# SPI_Level_Shifter.net
KiCad netlist of a schematic drawn in EAGLE
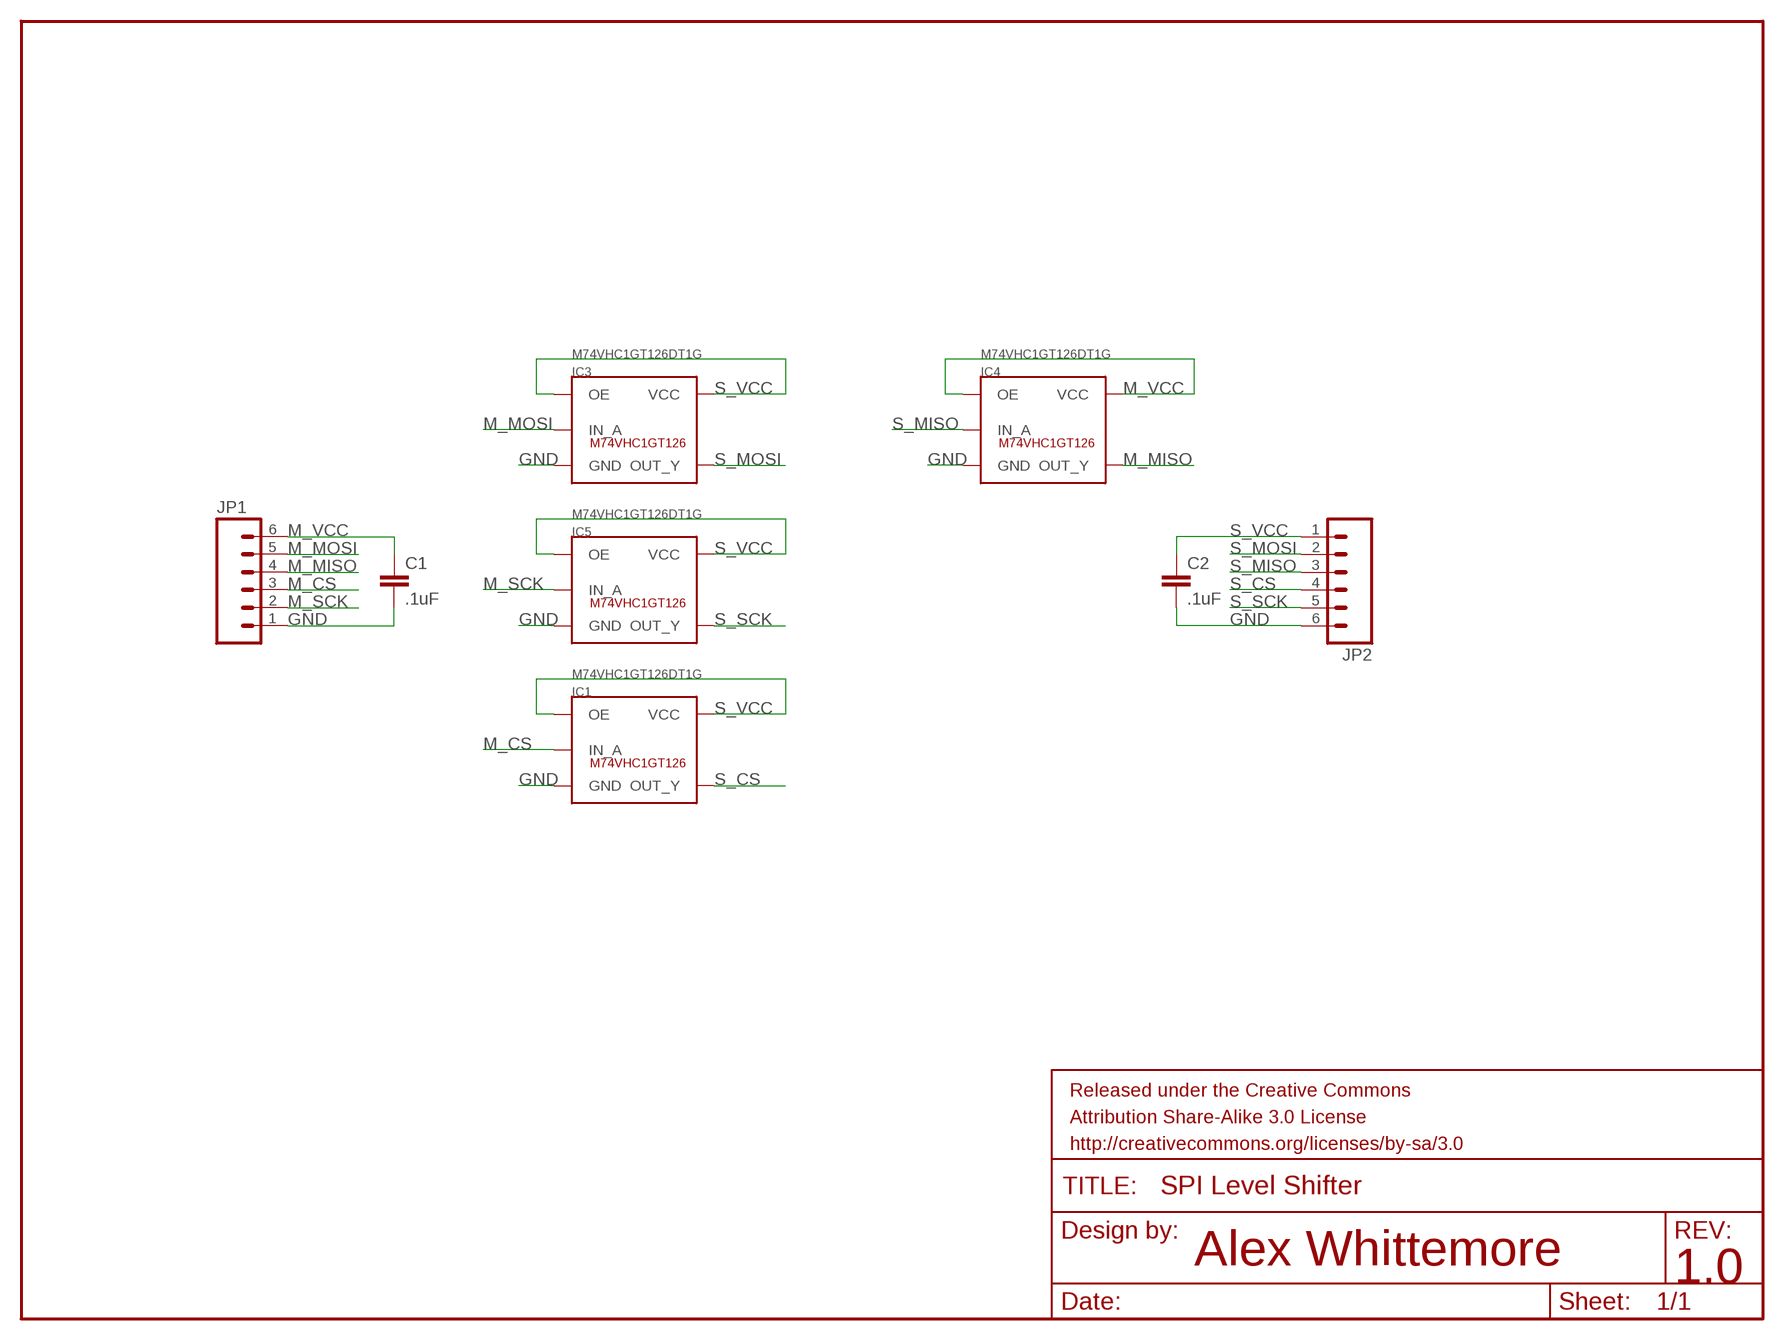
[diagram p0: schematic, sheet 1]

(export (version "E")
  (design (tool "Eeschema 10.0.6"))
  (components
    (comp (ref "C1")
      (value ".1uF")
      (footprint "eagle-import:0402-CAP")
      (libsource (lib "eagle-import") (part "CAP0402-CAP"))
    )
    (comp (ref "C2")
      (value ".1uF")
      (footprint "eagle-import:0402-CAP")
      (libsource (lib "eagle-import") (part "CAP0402-CAP"))
    )
    (comp (ref "IC1")
      (value "M74VHC1GT126DT1G")
      (footprint "eagle-import:SOT23-5L")
      (libsource (lib "eagle-import") (part "M74VHC1GT126DT1G"))
    )
    (comp (ref "IC3")
      (value "M74VHC1GT126DT1G")
      (footprint "eagle-import:SOT23-5L")
      (libsource (lib "eagle-import") (part "M74VHC1GT126DT1G"))
    )
    (comp (ref "IC4")
      (value "M74VHC1GT126DT1G")
      (footprint "eagle-import:SOT23-5L")
      (libsource (lib "eagle-import") (part "M74VHC1GT126DT1G"))
    )
    (comp (ref "IC5")
      (value "M74VHC1GT126DT1G")
      (footprint "eagle-import:SOT23-5L")
      (libsource (lib "eagle-import") (part "M74VHC1GT126DT1G"))
    )
    (comp (ref "JP1")
      (value "M06LOCK")
      (footprint "eagle-import:1X06_LOCK")
      (libsource (lib "eagle-import") (part "M06LOCK"))
    )
    (comp (ref "JP2")
      (value "M06LOCK")
      (footprint "eagle-import:1X06_LOCK")
      (libsource (lib "eagle-import") (part "M06LOCK"))
    )
  )
  (nets
    (net (code "1") (name "/GND") (class "Default")
      (node (ref "C1") (pin "2") (pinfunction "2_2") (pintype "passive"))
      (node (ref "C2") (pin "2") (pinfunction "2_2") (pintype "passive"))
      (node (ref "IC1") (pin "3") (pinfunction "GND_3") (pintype "bidirectional"))
      (node (ref "IC3") (pin "3") (pinfunction "GND_3") (pintype "bidirectional"))
      (node (ref "IC4") (pin "3") (pinfunction "GND_3") (pintype "bidirectional"))
      (node (ref "IC5") (pin "3") (pinfunction "GND_3") (pintype "bidirectional"))
      (node (ref "JP1") (pin "1") (pinfunction "1_1") (pintype "passive"))
      (node (ref "JP2") (pin "6") (pinfunction "6_6") (pintype "passive"))
    )
    (net (code "2") (name "/M_CS") (class "Default")
      (node (ref "IC1") (pin "2") (pinfunction "IN_A_2") (pintype "bidirectional"))
      (node (ref "JP1") (pin "3") (pinfunction "3_3") (pintype "passive"))
    )
    (net (code "3") (name "/M_MISO") (class "Default")
      (node (ref "IC4") (pin "4") (pinfunction "OUT_Y_4") (pintype "bidirectional"))
      (node (ref "JP1") (pin "4") (pinfunction "4_4") (pintype "passive"))
    )
    (net (code "4") (name "/M_MOSI") (class "Default")
      (node (ref "IC3") (pin "2") (pinfunction "IN_A_2") (pintype "bidirectional"))
      (node (ref "JP1") (pin "5") (pinfunction "5_5") (pintype "passive"))
    )
    (net (code "5") (name "/M_SCK") (class "Default")
      (node (ref "IC5") (pin "2") (pinfunction "IN_A_2") (pintype "bidirectional"))
      (node (ref "JP1") (pin "2") (pinfunction "2_2") (pintype "passive"))
    )
    (net (code "6") (name "/M_VCC") (class "Default")
      (node (ref "C1") (pin "1") (pinfunction "1_1") (pintype "passive"))
      (node (ref "IC4") (pin "1") (pinfunction "OE_1") (pintype "bidirectional"))
      (node (ref "IC4") (pin "5") (pinfunction "VCC_5") (pintype "bidirectional"))
      (node (ref "JP1") (pin "6") (pinfunction "6_6") (pintype "passive"))
    )
    (net (code "7") (name "/S_CS") (class "Default")
      (node (ref "IC1") (pin "4") (pinfunction "OUT_Y_4") (pintype "bidirectional"))
      (node (ref "JP2") (pin "4") (pinfunction "4_4") (pintype "passive"))
    )
    (net (code "8") (name "/S_MISO") (class "Default")
      (node (ref "IC4") (pin "2") (pinfunction "IN_A_2") (pintype "bidirectional"))
      (node (ref "JP2") (pin "3") (pinfunction "3_3") (pintype "passive"))
    )
    (net (code "9") (name "/S_MOSI") (class "Default")
      (node (ref "IC3") (pin "4") (pinfunction "OUT_Y_4") (pintype "bidirectional"))
      (node (ref "JP2") (pin "2") (pinfunction "2_2") (pintype "passive"))
    )
    (net (code "10") (name "/S_SCK") (class "Default")
      (node (ref "IC5") (pin "4") (pinfunction "OUT_Y_4") (pintype "bidirectional"))
      (node (ref "JP2") (pin "5") (pinfunction "5_5") (pintype "passive"))
    )
    (net (code "11") (name "/S_VCC") (class "Default")
      (node (ref "C2") (pin "1") (pinfunction "1_1") (pintype "passive"))
      (node (ref "IC1") (pin "1") (pinfunction "OE_1") (pintype "bidirectional"))
      (node (ref "IC1") (pin "5") (pinfunction "VCC_5") (pintype "bidirectional"))
      (node (ref "IC3") (pin "1") (pinfunction "OE_1") (pintype "bidirectional"))
      (node (ref "IC3") (pin "5") (pinfunction "VCC_5") (pintype "bidirectional"))
      (node (ref "IC5") (pin "1") (pinfunction "OE_1") (pintype "bidirectional"))
      (node (ref "IC5") (pin "5") (pinfunction "VCC_5") (pintype "bidirectional"))
      (node (ref "JP2") (pin "1") (pinfunction "1_1") (pintype "passive"))
    )
  )
)
